# aLCD.net
KiCad netlist of a schematic drawn in Altium Designer
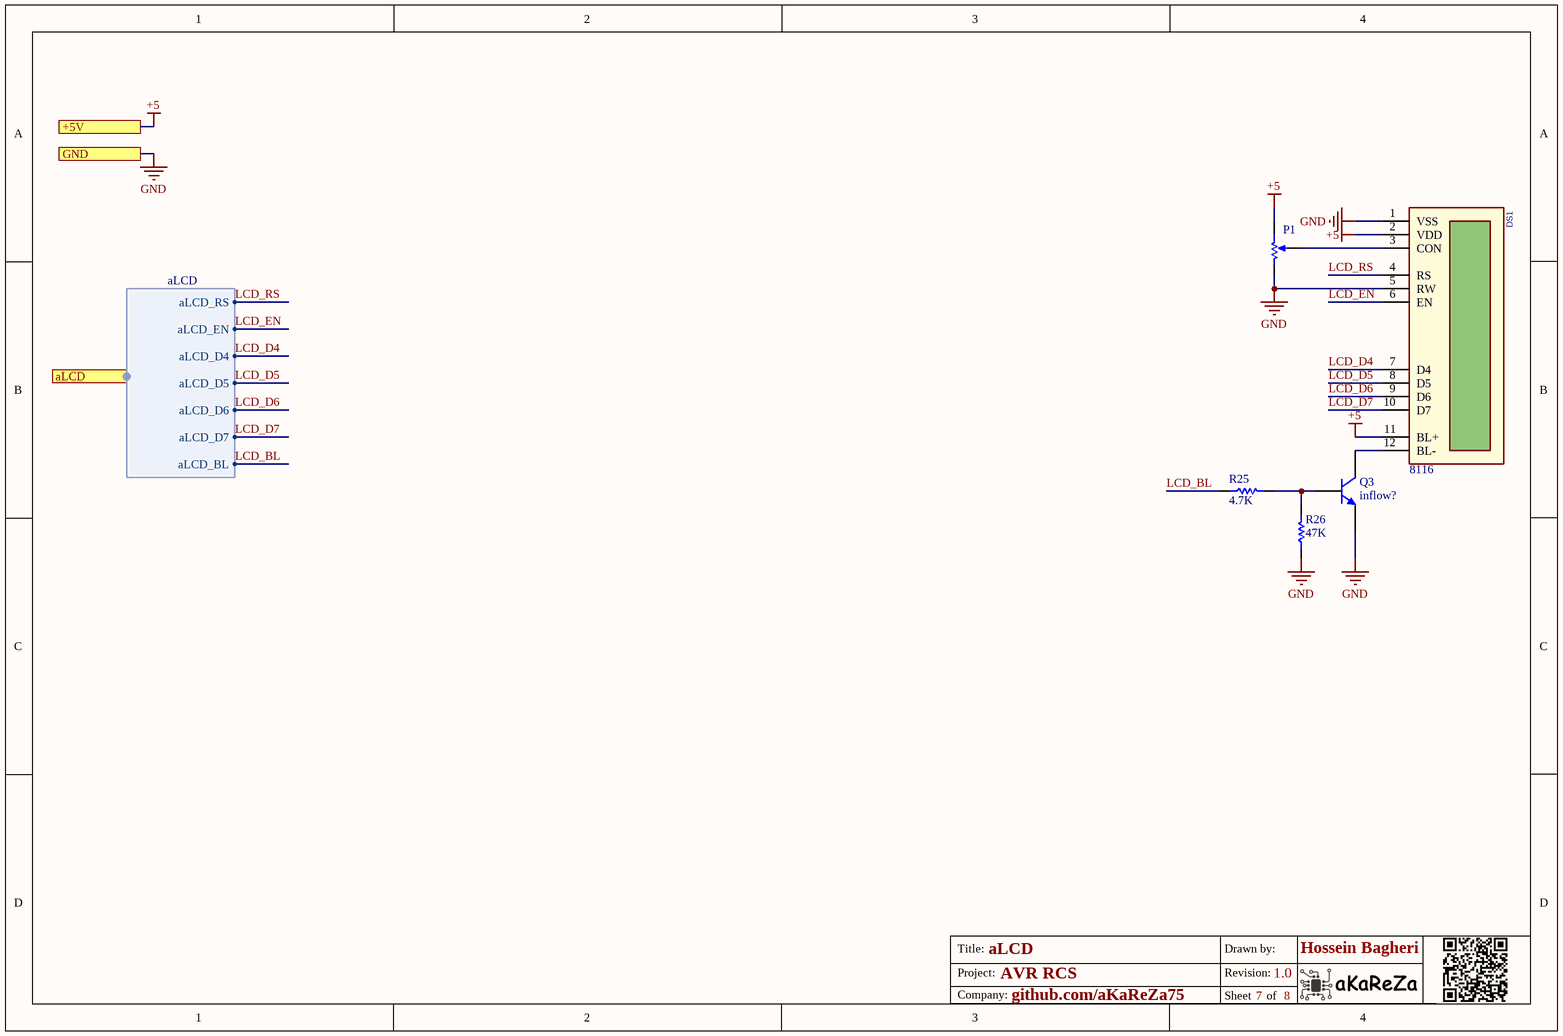
[diagram p0: aLCD.SchDoc]

(export (version "E")
  (design (tool "Eeschema 10.0.6"))
  (components
    (comp (ref "DS1")
      (value "16x2")
      (footprint "BOX-HDR-2x6-2.54mm-S")
      (description "Alphanumeric LCD character")
      (fields (field (name "INFLOW") "8116") (field (name "VALIDATION") "Valid"))
      (libsource (lib "aKaReZa") (part "ModSen_LCD_CH_16x2_Box"))
    )
    (comp (ref "P1")
      (value "10K")
      (footprint "Multi turn 01")
      (description "Multi Turn")
      (fields (field (name "VALIDATION") "Valid"))
      (libsource (lib "aKaReZa") (part "Res_Multi"))
    )
    (comp (ref "Q3")
      (value "NPN")
      (footprint "SOT23_N")
      (description "NPN General purpose Transistor")
      (fields (field (name "INFLOW") "inflow?") (field (name "VALIDATION") "Valid"))
      (libsource (lib "aKaReZa") (part "Semi_BJT_BC817"))
    )
    (comp (ref "R25")
      (value "4.7K")
      (footprint "RES 0805 (2012X06L)")
      (description "Resistor")
      (fields (field (name "VALIDATION") "Valid"))
      (libsource (lib "aKaReZa") (part "Res_SMD_0805"))
    )
    (comp (ref "R26")
      (value "47K")
      (footprint "RES 0805 (2012X06L)")
      (description "Resistor")
      (fields (field (name "VALIDATION") "Valid"))
      (libsource (lib "aKaReZa") (part "Res_SMD_0805"))
    )
  )
  (nets
    (net (code "2") (name "+5") (class "Default")
      (node (ref "DS1") (pin "11") (pinfunction "BL+_11") (pintype "passive"))
      (node (ref "DS1") (pin "2") (pinfunction "VDD_2") (pintype "passive"))
      (node (ref "P1") (pin "1") (pinfunction "3_1") (pintype "passive"))
    )
    (net (code "3") (name "/LCD_BL") (class "Default")
      (node (ref "R25") (pin "1") (pinfunction "1_1") (pintype "passive"))
    )
    (net (code "4") (name "/LCD_D4") (class "Default")
      (node (ref "DS1") (pin "7") (pinfunction "D4_7") (pintype "passive"))
    )
    (net (code "5") (name "/LCD_D5") (class "Default")
      (node (ref "DS1") (pin "8") (pinfunction "D5_8") (pintype "passive"))
    )
    (net (code "6") (name "/LCD_D6") (class "Default")
      (node (ref "DS1") (pin "9") (pinfunction "D6_9") (pintype "passive"))
    )
    (net (code "7") (name "/LCD_D7") (class "Default")
      (node (ref "DS1") (pin "10") (pinfunction "D7_10") (pintype "passive"))
    )
    (net (code "8") (name "/LCD_EN") (class "Default")
      (node (ref "DS1") (pin "6") (pinfunction "EN_6") (pintype "passive"))
    )
    (net (code "9") (name "/LCD_RS") (class "Default")
      (node (ref "DS1") (pin "4") (pinfunction "RS_4") (pintype "passive"))
    )
    (net (code "11") (name "GND") (class "Default")
      (node (ref "DS1") (pin "1") (pinfunction "VSS_1") (pintype "passive"))
      (node (ref "DS1") (pin "5") (pinfunction "RW_5") (pintype "passive"))
      (node (ref "P1") (pin "3") (pinfunction "1_3") (pintype "passive"))
      (node (ref "Q3") (pin "2") (pinfunction "E_2") (pintype "passive"))
      (node (ref "R26") (pin "1") (pinfunction "1_1") (pintype "passive"))
    )
    (net (code "12") (name "Net-(DS1-BL-)") (class "Default")
      (node (ref "DS1") (pin "12") (pinfunction "BL-_12") (pintype "passive"))
      (node (ref "Q3") (pin "3") (pinfunction "C_3") (pintype "passive"))
    )
    (net (code "13") (name "Net-(DS1-CON)") (class "Default")
      (node (ref "DS1") (pin "3") (pinfunction "CON_3") (pintype "passive"))
      (node (ref "P1") (pin "2") (pinfunction "2_2") (pintype "passive"))
    )
    (net (code "14") (name "Net-(Q3-B)") (class "Default")
      (node (ref "Q3") (pin "1") (pinfunction "B_1") (pintype "passive"))
      (node (ref "R25") (pin "2") (pinfunction "2_2") (pintype "passive"))
      (node (ref "R26") (pin "2") (pinfunction "2_2") (pintype "passive"))
    )
  )
)
